# Digital_Outputs.net
KiCad netlist of a schematic drawn in Altium Designer
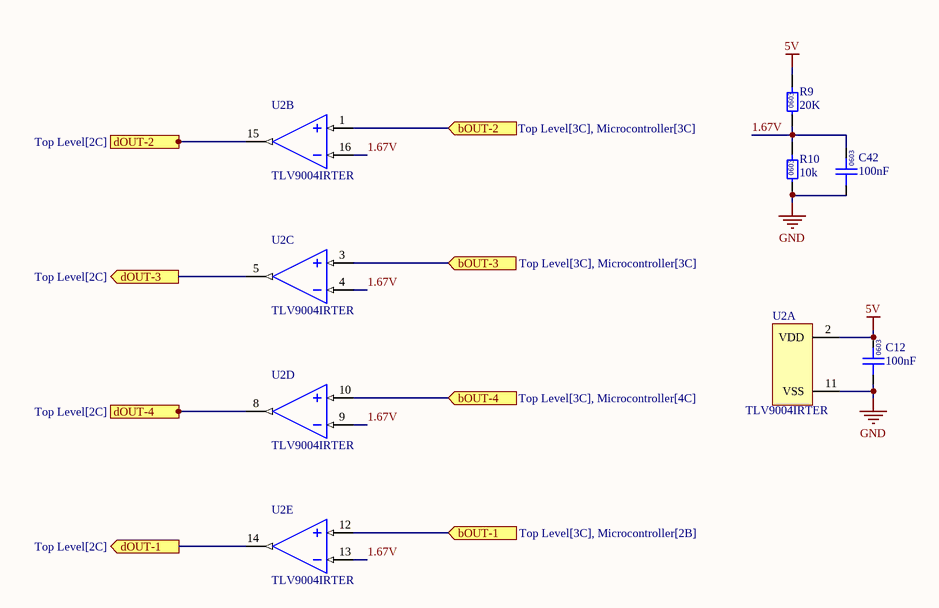
[diagram p0: Digital_Outputs.SchDoc]

(export (version "E")
  (design (tool "Eeschema 10.0.6"))
  (components
    (comp (ref "C12")
      (value "100nF")
      (footprint "0603")
      (fields
        (field (name "PART NUMBER") "GCM188L81H104KA57D")
        (field (name "MANUFACTURER") "muRata")
        (field (name "TOLERANCE") "±10%")
      )
      (libsource (lib "ts_standard_library") (part "Capacitor 0603"))
    )
    (comp (ref "C42")
      (value "100nF")
      (footprint "0603")
      (fields
        (field (name "PART NUMBER") "GCM188L81H104KA57D")
        (field (name "MANUFACTURER") "muRata")
        (field (name "TOLERANCE") "±10%")
      )
      (libsource (lib "ts_standard_library") (part "Capacitor 0603"))
    )
    (comp (ref "R9")
      (value "20K")
      (footprint "0603")
      (fields
        (field (name "PART NUMBER") "RC0603FR-0720KL")
        (field (name "MANUFACTURER") "YAGEO")
        (field (name "TOLERANCE") "0.01")
      )
      (libsource (lib "ts_standard_library") (part "Resistor 0603"))
    )
    (comp (ref "R10")
      (value "10k")
      (footprint "0603")
      (fields
        (field (name "PART NUMBER") "RC0603FR-0710KL")
        (field (name "MANUFACTURER") "YAGEO")
        (field (name "TOLERANCE") "0.01")
      )
      (libsource (lib "ts_standard_library") (part "Resistor 0603"))
    )
    (comp (ref "U2")
      (value "TLV9004IRTER")
      (footprint "TI 16-WQFN (3x3, 1.68mm)")
      (description "IC OPAMP GP 4 CIRCUIT 16WQFN")
      (fields
        (field (name "MANUFACTURER") "Texas Instruments")
        (field (name "DIGIKEY PART NUMBER") "296-51828-1-ND")
      )
      (libsource (lib "ts_standard_library") (part "TLV9004IRTER"))
    )
  )
  (nets
    (net (code "1") (name "/1.67V") (class "Default")
      (node (ref "C42") (pin "2") (pinfunction "2_2") (pintype "passive"))
      (node (ref "R10") (pin "2") (pinfunction "2_2") (pintype "passive"))
      (node (ref "R9") (pin "1") (pinfunction "1_1") (pintype "passive"))
      (node (ref "U2") (pin "13") (pinfunction "4IN-_13") (pintype "input"))
      (node (ref "U2") (pin "16") (pinfunction "1IN+_16") (pintype "input"))
      (node (ref "U2") (pin "4") (pinfunction "2IN-_4") (pintype "input"))
      (node (ref "U2") (pin "9") (pinfunction "3IN-_9") (pintype "input"))
    )
    (net (code "2") (name "/bOUT-1") (class "Default")
      (node (ref "U2") (pin "12") (pinfunction "4IN+_12") (pintype "input"))
    )
    (net (code "3") (name "/bOUT-2") (class "Default")
      (node (ref "U2") (pin "1") (pinfunction "1IN+_1") (pintype "input"))
    )
    (net (code "4") (name "/bOUT-3") (class "Default")
      (node (ref "U2") (pin "3") (pinfunction "2IN+_3") (pintype "input"))
    )
    (net (code "5") (name "/bOUT-4") (class "Default")
      (node (ref "U2") (pin "10") (pinfunction "3IN+_10") (pintype "input"))
    )
    (net (code "6") (name "/dOUT-1") (class "Default")
      (node (ref "U2") (pin "14") (pinfunction "4OUT_14") (pintype "output"))
    )
    (net (code "7") (name "/dOUT-2") (class "Default")
      (node (ref "U2") (pin "15") (pinfunction "1OUT_15") (pintype "output"))
    )
    (net (code "8") (name "/dOUT-3") (class "Default")
      (node (ref "U2") (pin "5") (pinfunction "2OUT_5") (pintype "output"))
    )
    (net (code "9") (name "/dOUT-4") (class "Default")
      (node (ref "U2") (pin "8") (pinfunction "3OUT_8") (pintype "output"))
    )
    (net (code "10") (name "5V") (class "Default")
      (node (ref "C12") (pin "2") (pinfunction "2_2") (pintype "passive"))
      (node (ref "R9") (pin "2") (pinfunction "2_2") (pintype "passive"))
      (node (ref "U2") (pin "2") (pinfunction "VDD_2") (pintype "power_in"))
    )
    (net (code "11") (name "GND") (class "Default")
      (node (ref "C12") (pin "1") (pinfunction "1_1") (pintype "passive"))
      (node (ref "C42") (pin "1") (pinfunction "1_1") (pintype "passive"))
      (node (ref "R10") (pin "1") (pinfunction "1_1") (pintype "passive"))
      (node (ref "U2") (pin "11") (pinfunction "VSS_11") (pintype "power_in"))
    )
  )
)
